# BLDC_DRV_F1.net
KiCad netlist of a schematic drawn in Altium Designer
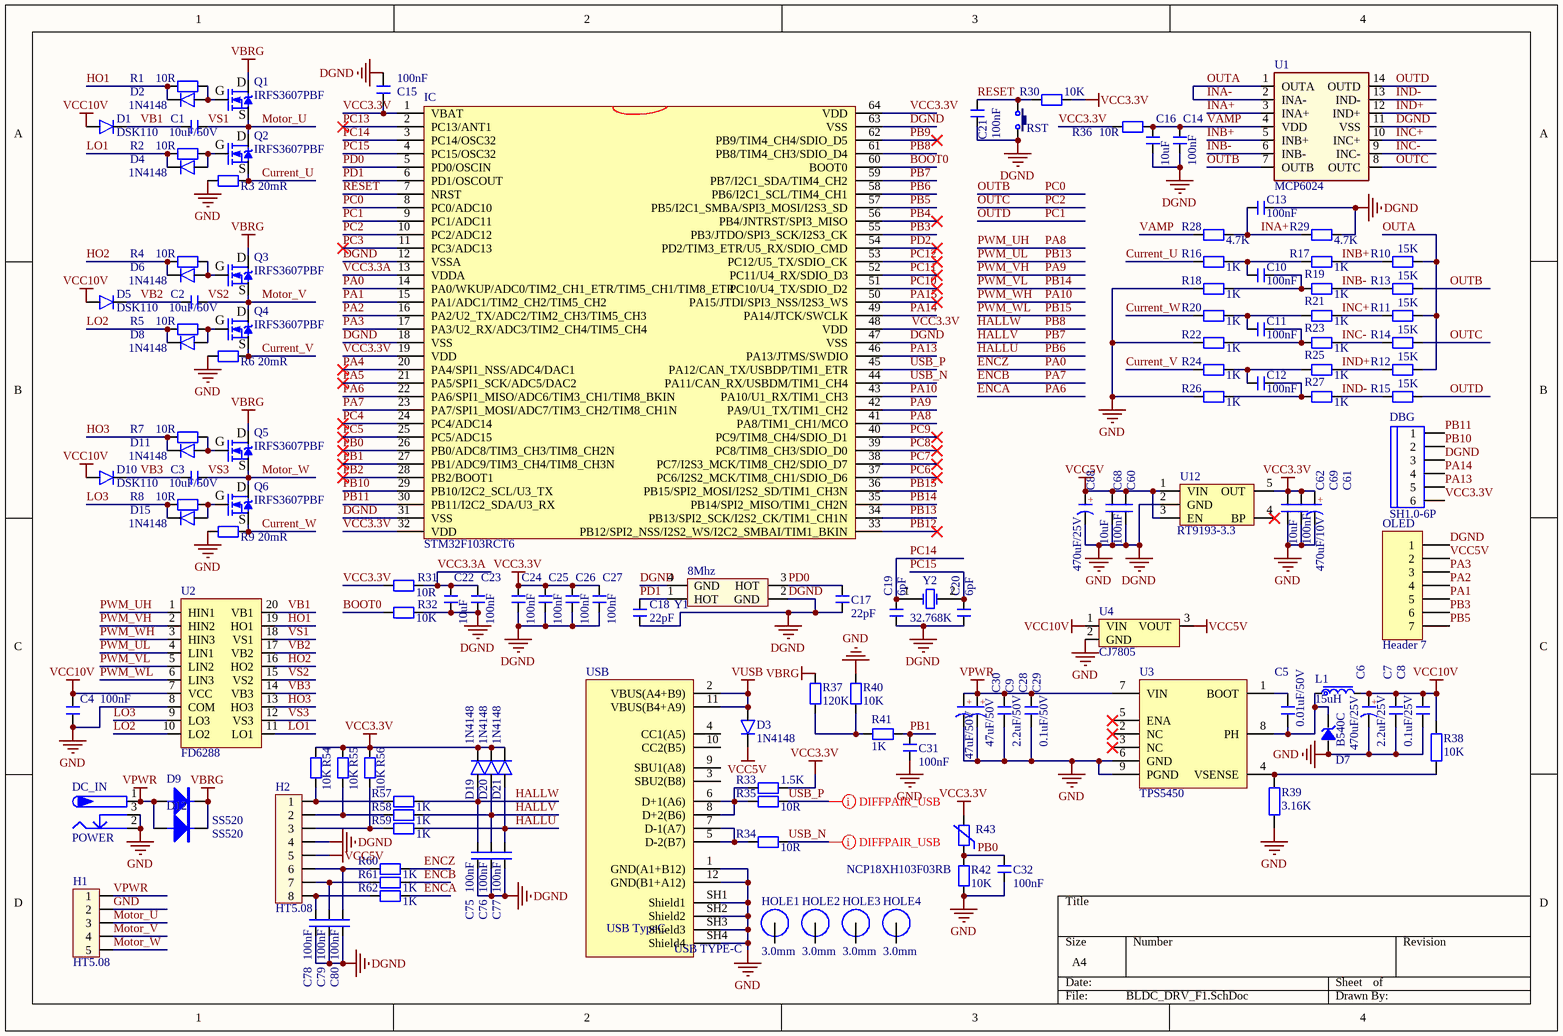
[diagram p0: BLDC_DRV_F1.SchDoc]

(export (version "E")
  (design (tool "Eeschema 10.0.6"))
  (components
    (comp (ref "C1")
      (value "10uF/50V")
      (footprint "C 0603_L")
      (description "无极性贴片电容")
      (libsource (lib "LovelessingSch") (part "C"))
    )
    (comp (ref "C2")
      (value "10uF/50V")
      (footprint "C 0603_L")
      (description "无极性贴片电容")
      (libsource (lib "LovelessingSch") (part "C"))
    )
    (comp (ref "C3")
      (value "10uF/50V")
      (footprint "C 0603_L")
      (description "无极性贴片电容")
      (libsource (lib "LovelessingSch") (part "C"))
    )
    (comp (ref "C4")
      (value "100nF")
      (footprint "C 0603_L")
      (description "无极性贴片电容")
      (fields (field (name "版权归属") "源创客"))
      (libsource (lib "电阻-电容-电感") (part "C"))
    )
    (comp (ref "C5")
      (value "0.01uF/50V")
      (footprint "C 0805_L")
      (description "无极性贴片电容")
      (libsource (lib "") (part "C_1"))
    )
    (comp (ref "C6")
      (value "470uF/25V")
      (footprint "CM D(6.3*7.7)")
      (description "贴片电解电容")
      (libsource (lib "LovelessingSch") (part "C-CM"))
    )
    (comp (ref "C7")
      (value "2.2uF/25V")
      (footprint "C 0603_L")
      (description "无极性贴片电容")
      (libsource (lib "") (part "C_1"))
    )
    (comp (ref "C8")
      (value "0.1uF/25V")
      (footprint "C 0603_L")
      (description "无极性贴片电容")
      (libsource (lib "") (part "C_1"))
    )
    (comp (ref "C9")
      (value "47uF/50V")
      (footprint "CM D(6.3*7.7)")
      (description "贴片电解电容")
      (libsource (lib "LovelessingSch") (part "C-CM"))
    )
    (comp (ref "C10")
      (value "100nF")
      (footprint "C 0603_L")
      (description "无极性贴片电容")
      (libsource (lib "LovelessingSch") (part "C"))
    )
    (comp (ref "C11")
      (value "100nF")
      (footprint "C 0603_L")
      (description "无极性贴片电容")
      (libsource (lib "LovelessingSch") (part "C"))
    )
    (comp (ref "C12")
      (value "100nF")
      (footprint "C 0603_L")
      (description "无极性贴片电容")
      (libsource (lib "LovelessingSch") (part "C"))
    )
    (comp (ref "C13")
      (value "100nF")
      (footprint "C 0603_L")
      (description "无极性贴片电容")
      (libsource (lib "LovelessingSch") (part "C"))
    )
    (comp (ref "C14")
      (value "100nF")
      (footprint "C 0603_L")
      (description "无极性贴片电容")
      (libsource (lib "LovelessingSch") (part "C"))
    )
    (comp (ref "C15")
      (value "100nF")
      (footprint "C 0603_L")
      (description "无极性贴片电容")
      (fields (field (name "版权归属") "源创客"))
      (libsource (lib "电阻-电容-电感") (part "C"))
    )
    (comp (ref "C16")
      (value "10uF")
      (footprint "C 0603_L")
      (description "无极性贴片电容")
      (libsource (lib "LovelessingSch") (part "C"))
    )
    (comp (ref "C17")
      (value "22pF")
      (footprint "C 0603_L")
      (description "无极性贴片电容")
      (libsource (lib "LovelessingSch") (part "C"))
    )
    (comp (ref "C18")
      (value "22pF")
      (footprint "C 0603_L")
      (description "无极性贴片电容")
      (libsource (lib "LovelessingSch") (part "C"))
    )
    (comp (ref "C19")
      (value "6pF")
      (footprint "C 0603_L")
      (description "无极性贴片电容")
      (libsource (lib "LovelessingSch") (part "C"))
    )
    (comp (ref "C20")
      (value "6pF")
      (footprint "C 0603_L")
      (description "无极性贴片电容")
      (libsource (lib "LovelessingSch") (part "C"))
    )
    (comp (ref "C21")
      (value "100nF")
      (footprint "C 0603_L")
      (description "无极性贴片电容")
      (libsource (lib "LovelessingSch") (part "C"))
    )
    (comp (ref "C22")
      (value "10uF")
      (footprint "C 0603_L")
      (description "无极性贴片电容")
      (libsource (lib "LovelessingSch") (part "C"))
    )
    (comp (ref "C23")
      (value "100nF")
      (footprint "C 0603_L")
      (description "无极性贴片电容")
      (libsource (lib "LovelessingSch") (part "C"))
    )
    (comp (ref "C24")
      (value "100nF")
      (footprint "C 0603_L")
      (description "无极性贴片电容")
      (libsource (lib "LovelessingSch") (part "C"))
    )
    (comp (ref "C25")
      (value "100nF")
      (footprint "C 0603_L")
      (description "无极性贴片电容")
      (libsource (lib "LovelessingSch") (part "C"))
    )
    (comp (ref "C26")
      (value "100nF")
      (footprint "C 0603_L")
      (description "无极性贴片电容")
      (libsource (lib "LovelessingSch") (part "C"))
    )
    (comp (ref "C27")
      (value "100nF")
      (footprint "C 0603_L")
      (description "无极性贴片电容")
      (libsource (lib "LovelessingSch") (part "C"))
    )
    (comp (ref "C28")
      (value "2.2uF/50V")
      (footprint "C 0805_L")
      (description "无极性贴片电容")
      (libsource (lib "") (part "C_1"))
    )
    (comp (ref "C29")
      (value "0.1uF/50V")
      (footprint "C 0805_L")
      (description "无极性贴片电容")
      (libsource (lib "") (part "C_1"))
    )
    (comp (ref "C30")
      (value "47uF/50V")
      (footprint "CM D(6.3*7.7)")
      (description "贴片电解电容")
      (libsource (lib "LovelessingSch") (part "C-CM"))
    )
    (comp (ref "C31")
      (value "100nF")
      (footprint "C 0603_L")
      (description "无极性贴片电容")
      (libsource (lib "LovelessingSch") (part "C"))
    )
    (comp (ref "C32")
      (value "100nF")
      (footprint "C 0603_L")
      (description "无极性贴片电容")
      (libsource (lib "LovelessingSch") (part "C"))
    )
    (comp (ref "C60")
      (value "100nF")
      (footprint "C 0603_L")
      (description "无极性贴片电容")
      (libsource (lib "电阻-电容-电感") (part "C"))
    )
    (comp (ref "C61")
      (value "470uF/10V")
      (footprint "CM D(6.3*7.7)")
      (description "贴片电解电容")
      (libsource (lib "LovelessingSch") (part "C-CM"))
    )
    (comp (ref "C62")
      (value "10uF")
      (footprint "C 0603_L")
      (description "无极性贴片电容")
      (libsource (lib "电阻-电容-电感") (part "C"))
    )
    (comp (ref "C68")
      (value "10uF")
      (footprint "C 0603_L")
      (description "无极性贴片电容")
      (libsource (lib "电阻-电容-电感") (part "C"))
    )
    (comp (ref "C69")
      (value "100nF")
      (footprint "C 0603_L")
      (description "无极性贴片电容")
      (libsource (lib "电阻-电容-电感") (part "C"))
    )
    (comp (ref "C75")
      (value "100nF")
      (footprint "C 0603_L")
      (description "无极性贴片电容")
      (libsource (lib "LovelessingSch") (part "C"))
    )
    (comp (ref "C76")
      (value "100nF")
      (footprint "C 0603_L")
      (description "无极性贴片电容")
      (libsource (lib "LovelessingSch") (part "C"))
    )
    (comp (ref "C77")
      (value "100nF")
      (footprint "C 0603_L")
      (description "无极性贴片电容")
      (libsource (lib "LovelessingSch") (part "C"))
    )
    (comp (ref "C78")
      (value "100nF")
      (footprint "C 0603_L")
      (description "无极性贴片电容")
      (libsource (lib "LovelessingSch") (part "C"))
    )
    (comp (ref "C79")
      (value "100nF")
      (footprint "C 0603_L")
      (description "无极性贴片电容")
      (libsource (lib "LovelessingSch") (part "C"))
    )
    (comp (ref "C80")
      (value "100nF")
      (footprint "C 0603_L")
      (description "无极性贴片电容")
      (libsource (lib "LovelessingSch") (part "C"))
    )
    (comp (ref "C88")
      (value "470uF/25V")
      (footprint "CM D(6.3*7.7)")
      (description "贴片电解电容")
      (libsource (lib "LovelessingSch") (part "C-CM"))
    )
    (comp (ref "D1")
      (value "DSK110")
      (footprint "SOD-323")
      (description "二极管")
      (libsource (lib "LovelessingSch") (part "D"))
    )
    (comp (ref "D2")
      (value "1N4148")
      (footprint "SOD-323")
      (description "二极管")
      (libsource (lib "LovelessingSch") (part "D"))
    )
    (comp (ref "D3")
      (value "1N4148")
      (footprint "SOD-323")
      (description "二极管")
      (libsource (lib "LovelessingSch") (part "D"))
    )
    (comp (ref "D4")
      (value "1N4148")
      (footprint "SOD-323")
      (description "二极管")
      (libsource (lib "LovelessingSch") (part "D"))
    )
    (comp (ref "D5")
      (value "DSK110")
      (footprint "SOD-323")
      (description "二极管")
      (libsource (lib "LovelessingSch") (part "D"))
    )
    (comp (ref "D6")
      (value "1N4148")
      (footprint "SOD-323")
      (description "二极管")
      (libsource (lib "LovelessingSch") (part "D"))
    )
    (comp (ref "D7")
      (value "B540C")
      (footprint "LovelessingPcb:SMB")
      (description "TVS二极管")
      (libsource (lib "LovelessingSch") (part "D-ZMM3V6"))
    )
    (comp (ref "D8")
      (value "1N4148")
      (footprint "SOD-323")
      (description "二极管")
      (libsource (lib "LovelessingSch") (part "D"))
    )
    (comp (ref "D9")
      (value "SS520")
      (footprint "LovelessingPcb:SMC")
      (description "整流二极管")
      (libsource (lib "LovelessingSch") (part "DIODE"))
    )
    (comp (ref "D10")
      (value "DSK110")
      (footprint "SOD-323")
      (description "二极管")
      (libsource (lib "LovelessingSch") (part "D"))
    )
    (comp (ref "D11")
      (value "1N4148")
      (footprint "SOD-323")
      (description "二极管")
      (libsource (lib "LovelessingSch") (part "D"))
    )
    (comp (ref "D12")
      (value "SS520")
      (footprint "LovelessingPcb:SMC")
      (description "整流二极管")
      (libsource (lib "LovelessingSch") (part "DIODE"))
    )
    (comp (ref "D15")
      (value "1N4148")
      (footprint "SOD-323")
      (description "二极管")
      (libsource (lib "LovelessingSch") (part "D"))
    )
    (comp (ref "D19")
      (value "1N4148")
      (footprint "SOD-323")
      (description "二极管")
      (libsource (lib "LovelessingSch") (part "D"))
    )
    (comp (ref "D20")
      (value "1N4148")
      (footprint "SOD-323")
      (description "二极管")
      (libsource (lib "LovelessingSch") (part "D"))
    )
    (comp (ref "D21")
      (value "1N4148")
      (footprint "SOD-323")
      (description "二极管")
      (libsource (lib "LovelessingSch") (part "D"))
    )
    (comp (ref "DBG") (value "SH1.0-6P") (footprint "SH1.0_6P") (libsource (lib "MiniFly ") (part "HEAD6")))
    (comp (ref "DC_IN")
      (value "POWER")
      (footprint "DC10B")
      (description "低压电源接口")
      (libsource (lib "IMX6UL_ALPHA(底板)_V2.0") (part "P-DC"))
    )
    (comp (ref "H1")
      (value "HT5.08")
      (footprint "KF7620-5P")
      (description "端子")
      (libsource (lib "LovelessingSch") (part "Header_5P"))
    )
    (comp (ref "H2")
      (value "HT5.08")
      (footprint "SH1.0 S-W-8P")
      (description "端子")
      (libsource (lib "LovelessingSch") (part "Header_8P"))
    )
    (comp (ref "HOLE1")
      (value "3.0mm")
      (footprint "M3")
      (description "螺丝焊盘")
      (fields (field (name "Comment") "HOLE"))
      (libsource (lib "LovelessingSch") (part "HOLE"))
    )
    (comp (ref "HOLE2")
      (value "3.0mm")
      (footprint "M3")
      (description "螺丝焊盘")
      (fields (field (name "Comment") "HOLE"))
      (libsource (lib "LovelessingSch") (part "HOLE"))
    )
    (comp (ref "HOLE3")
      (value "3.0mm")
      (footprint "M3")
      (description "螺丝焊盘")
      (fields (field (name "Comment") "HOLE"))
      (libsource (lib "LovelessingSch") (part "HOLE"))
    )
    (comp (ref "HOLE4")
      (value "3.0mm")
      (footprint "M3")
      (description "螺丝焊盘")
      (fields (field (name "Comment") "HOLE"))
      (libsource (lib "LovelessingSch") (part "HOLE"))
    )
    (comp (ref "IC")
      (value "STM32F103RCT6")
      (footprint "LQFP64-10*10")
      (libsource (lib "MiniSTM32 V3.0封装库") (part "STM32F103RDT6"))
    )
    (comp (ref "L1")
      (value "15uH")
      (footprint "CDRH73")
      (description "功率屏蔽电感")
      (libsource (lib "LovelessingSch") (part "L-CDRH"))
    )
    (comp (ref "OLED")
      (value "Header 7")
      (footprint "HDR2.54-M-LI-7P")
      (description "Header, 7-Pin")
      (fields (field (name "PUBLISHER") "Altium Limited"))
      (libsource (lib "Miscellaneous Connectors") (part "Header 7"))
    )
    (comp (ref "Q1")
      (value "IRFS3607PBF")
      (footprint "TO263-3B")
      (description "NMOS 75V+80A 7.4mΩ")
      (libsource (lib "LovelessingSch") (part "IRFS3607PBF"))
    )
    (comp (ref "Q2")
      (value "IRFS3607PBF")
      (footprint "TO263-3B")
      (description "NMOS 75V+80A 7.4mΩ")
      (libsource (lib "LovelessingSch") (part "IRFS3607PBF"))
    )
    (comp (ref "Q3")
      (value "IRFS3607PBF")
      (footprint "TO263-3B")
      (description "NMOS 75V+80A 7.4mΩ")
      (libsource (lib "LovelessingSch") (part "IRFS3607PBF"))
    )
    (comp (ref "Q4")
      (value "IRFS3607PBF")
      (footprint "TO263-3B")
      (description "NMOS 75V+80A 7.4mΩ")
      (libsource (lib "LovelessingSch") (part "IRFS3607PBF"))
    )
    (comp (ref "Q5")
      (value "IRFS3607PBF")
      (footprint "TO263-3B")
      (description "NMOS 75V+80A 7.4mΩ")
      (libsource (lib "LovelessingSch") (part "IRFS3607PBF"))
    )
    (comp (ref "Q6")
      (value "IRFS3607PBF")
      (footprint "TO263-3B")
      (description "NMOS 75V+80A 7.4mΩ")
      (libsource (lib "LovelessingSch") (part "IRFS3607PBF"))
    )
    (comp (ref "R1")
      (value "10R")
      (footprint "R 0603_L")
      (description "贴片电阻")
      (libsource (lib "LovelessingSch") (part "R"))
    )
    (comp (ref "R2")
      (value "10R")
      (footprint "R 0603_L")
      (description "贴片电阻")
      (libsource (lib "LovelessingSch") (part "R"))
    )
    (comp (ref "R3")
      (value "20mR")
      (footprint "R 2512_L")
      (description "贴片电阻")
      (libsource (lib "LovelessingSch") (part "R"))
    )
    (comp (ref "R4")
      (value "10R")
      (footprint "R 0603_L")
      (description "贴片电阻")
      (libsource (lib "LovelessingSch") (part "R"))
    )
    (comp (ref "R5")
      (value "10R")
      (footprint "R 0603_L")
      (description "贴片电阻")
      (libsource (lib "LovelessingSch") (part "R"))
    )
    (comp (ref "R6")
      (value "20mR")
      (footprint "R 2512_L")
      (description "贴片电阻")
      (libsource (lib "LovelessingSch") (part "R"))
    )
    (comp (ref "R7")
      (value "10R")
      (footprint "R 0603_L")
      (description "贴片电阻")
      (libsource (lib "LovelessingSch") (part "R"))
    )
    (comp (ref "R8")
      (value "10R")
      (footprint "R 0603_L")
      (description "贴片电阻")
      (libsource (lib "LovelessingSch") (part "R"))
    )
    (comp (ref "R9")
      (value "20mR")
      (footprint "R 2512_L")
      (description "贴片电阻")
      (libsource (lib "LovelessingSch") (part "R"))
    )
    (comp (ref "R10")
      (value "15K")
      (footprint "R 0603_L")
      (description "贴片电阻")
      (libsource (lib "LovelessingSch") (part "R"))
    )
    (comp (ref "R11")
      (value "15K")
      (footprint "R 0603_L")
      (description "贴片电阻")
      (libsource (lib "LovelessingSch") (part "R"))
    )
    (comp (ref "R12")
      (value "15K")
      (footprint "R 0603_L")
      (description "贴片电阻")
      (libsource (lib "LovelessingSch") (part "R"))
    )
    (comp (ref "R13")
      (value "15K")
      (footprint "R 0603_L")
      (description "贴片电阻")
      (libsource (lib "LovelessingSch") (part "R"))
    )
    (comp (ref "R14")
      (value "15K")
      (footprint "R 0603_L")
      (description "贴片电阻")
      (libsource (lib "LovelessingSch") (part "R"))
    )
    (comp (ref "R15")
      (value "15K")
      (footprint "R 0603_L")
      (description "贴片电阻")
      (libsource (lib "LovelessingSch") (part "R"))
    )
    (comp (ref "R16")
      (value "1K")
      (footprint "R 0603_L")
      (description "贴片电阻")
      (libsource (lib "LovelessingSch") (part "R"))
    )
    (comp (ref "R17")
      (value "1K")
      (footprint "R 0603_L")
      (description "贴片电阻")
      (libsource (lib "LovelessingSch") (part "R"))
    )
    (comp (ref "R18")
      (value "1K")
      (footprint "R 0603_L")
      (description "贴片电阻")
      (libsource (lib "LovelessingSch") (part "R"))
    )
    (comp (ref "R19")
      (value "1K")
      (footprint "R 0603_L")
      (description "贴片电阻")
      (libsource (lib "LovelessingSch") (part "R"))
    )
    (comp (ref "R20")
      (value "1K")
      (footprint "R 0603_L")
      (description "贴片电阻")
      (libsource (lib "LovelessingSch") (part "R"))
    )
    (comp (ref "R21")
      (value "1K")
      (footprint "R 0603_L")
      (description "贴片电阻")
      (libsource (lib "LovelessingSch") (part "R"))
    )
    (comp (ref "R22")
      (value "1K")
      (footprint "R 0603_L")
      (description "贴片电阻")
      (libsource (lib "LovelessingSch") (part "R"))
    )
    (comp (ref "R23")
      (value "1K")
      (footprint "R 0603_L")
      (description "贴片电阻")
      (libsource (lib "LovelessingSch") (part "R"))
    )
    (comp (ref "R24")
      (value "1K")
      (footprint "R 0603_L")
      (description "贴片电阻")
      (libsource (lib "LovelessingSch") (part "R"))
    )
    (comp (ref "R25")
      (value "1K")
      (footprint "R 0603_L")
      (description "贴片电阻")
      (libsource (lib "LovelessingSch") (part "R"))
    )
    (comp (ref "R26")
      (value "1K")
      (footprint "R 0603_L")
      (description "贴片电阻")
      (libsource (lib "LovelessingSch") (part "R"))
    )
    (comp (ref "R27")
      (value "1K")
      (footprint "R 0603_L")
      (description "贴片电阻")
      (libsource (lib "LovelessingSch") (part "R"))
    )
    (comp (ref "R28")
      (value "4.7K")
      (footprint "R 0603_L")
      (description "贴片电阻")
      (libsource (lib "LovelessingSch") (part "R"))
    )
    (comp (ref "R29")
      (value "4.7K")
      (footprint "R 0603_L")
      (description "贴片电阻")
      (libsource (lib "LovelessingSch") (part "R"))
    )
    (comp (ref "R30")
      (value "10K")
      (footprint "R 0603_L")
      (description "贴片电阻")
      (libsource (lib "LovelessingSch") (part "R"))
    )
    (comp (ref "R31")
      (value "10R")
      (footprint "R 0603_L")
      (description "贴片电阻")
      (libsource (lib "LovelessingSch") (part "R"))
    )
    (comp (ref "R32")
      (value "10K")
      (footprint "R 0603_L")
      (description "贴片电阻")
      (libsource (lib "LovelessingSch") (part "R"))
    )
    (comp (ref "R33")
      (value "1.5K")
      (footprint "R 0603_L")
      (description "贴片电阻")
      (libsource (lib "LovelessingSch") (part "R"))
    )
    (comp (ref "R34")
      (value "10R")
      (footprint "R 0603_L")
      (description "贴片电阻")
      (libsource (lib "LovelessingSch") (part "R"))
    )
    (comp (ref "R35")
      (value "10R")
      (footprint "R 0603_L")
      (description "贴片电阻")
      (libsource (lib "LovelessingSch") (part "R"))
    )
    (comp (ref "R36")
      (value "10R")
      (footprint "R 0603_L")
      (description "贴片电阻")
      (libsource (lib "LovelessingSch") (part "R"))
    )
    (comp (ref "R37")
      (value "120K")
      (footprint "R 0603_L")
      (description "贴片电阻")
      (libsource (lib "LovelessingSch") (part "R"))
    )
    (comp (ref "R38")
      (value "10K")
      (footprint "R 0603_L")
      (description "贴片电阻")
      (libsource (lib "") (part "R_1"))
    )
    (comp (ref "R39")
      (value "3.16K")
      (footprint "R 0603_L")
      (description "贴片电阻")
      (libsource (lib "") (part "R_1"))
    )
    (comp (ref "R40")
      (value "10K")
      (footprint "R 0603_L")
      (description "贴片电阻")
      (libsource (lib "LovelessingSch") (part "R"))
    )
    (comp (ref "R41")
      (value "1K")
      (footprint "R 0603_L")
      (description "贴片电阻")
      (libsource (lib "LovelessingSch") (part "R"))
    )
    (comp (ref "R42")
      (value "10K")
      (footprint "R 0603_L")
      (description "贴片电阻")
      (libsource (lib "LovelessingSch") (part "R"))
    )
    (comp (ref "R43")
      (value "NCP18XH103F03RB")
      (footprint "R 0603_L")
      (description "热敏电阻")
      (libsource (lib "LovelessingSch") (part "R_NTC"))
    )
    (comp (ref "R54")
      (value "10K")
      (footprint "R 0603_L")
      (description "贴片电阻")
      (libsource (lib "LovelessingSch") (part "R"))
    )
    (comp (ref "R55")
      (value "10K")
      (footprint "R 0603_L")
      (description "贴片电阻")
      (libsource (lib "LovelessingSch") (part "R"))
    )
    (comp (ref "R56")
      (value "10K")
      (footprint "R 0603_L")
      (description "贴片电阻")
      (libsource (lib "LovelessingSch") (part "R"))
    )
    (comp (ref "R57")
      (value "1K")
      (footprint "R 0603_L")
      (description "贴片电阻")
      (libsource (lib "LovelessingSch") (part "R"))
    )
    (comp (ref "R58")
      (value "1K")
      (footprint "R 0603_L")
      (description "贴片电阻")
      (libsource (lib "LovelessingSch") (part "R"))
    )
    (comp (ref "R59")
      (value "1K")
      (footprint "R 0603_L")
      (description "贴片电阻")
      (libsource (lib "LovelessingSch") (part "R"))
    )
    (comp (ref "R60")
      (value "1K")
      (footprint "R 0603_L")
      (description "贴片电阻")
      (libsource (lib "LovelessingSch") (part "R"))
    )
    (comp (ref "R61")
      (value "1K")
      (footprint "R 0603_L")
      (description "贴片电阻")
      (libsource (lib "LovelessingSch") (part "R"))
    )
    (comp (ref "R62")
      (value "1K")
      (footprint "R 0603_L")
      (description "贴片电阻")
      (libsource (lib "LovelessingSch") (part "R"))
    )
    (comp (ref "RST")
      (value "KEY")
      (footprint "TSW SMD-3*6*2.5")
      (description "按键")
      (libsource (lib "LovelessingSch") (part "KEY"))
    )
    (comp (ref "U1") (value "MCP6024") (footprint "SOP14_L") (libsource (lib "MINIBLDC") (part "MCP6024")))
    (comp (ref "U2") (value "FD6288") (footprint "TSSOP20_L") (libsource (lib "MINIBLDC") (part "FD6288")))
    (comp (ref "U3")
      (value "TPS5450")
      (footprint "SOP8_G")
      (description "降压电源芯片")
      (libsource (lib "Schlib1") (part "TPS5450"))
    )
    (comp (ref "U4")
      (value "CJ7805")
      (footprint "TO263_3B")
      (description "7805 5V")
      (libsource (lib "LovelessingSch") (part "CJ7805"))
    )
    (comp (ref "U12")
      (value "RT9193-3.3")
      (footprint "SOT23-5L")
      (description "LDO")
      (libsource (lib "LDO和DCDC") (part "LDO RT9193"))
    )
    (comp (ref "USB")
      (value "USB TypeC")
      (footprint "USB Type-C")
      (description "12P TypeC 母座")
      (libsource (lib "正点原子封装库V1.0") (part "USB 2.0 Type C"))
    )
    (comp (ref "Y1")
      (value "8Mhz")
      (footprint "XTAL-3225")
      (description "3225贴片无源晶振")
      (libsource (lib "ALIENTEK_COMPONENT") (part "XTAL_3225"))
    )
    (comp (ref "Y2")
      (value "32.768K")
      (footprint "OSC 3215-2P")
      (description "Crystal Oscillator")
      (fields (field (name "PUBLISHER") "Altium Limited"))
      (libsource (lib "WarShip V3 STM32103封装库") (part "XTAL"))
    )
  )
  (nets
    (net (code "1") (name "/BOOT0") (class "Default")
      (node (ref "IC") (pin "60") (pinfunction "BOOT0_60") (pintype "passive"))
      (node (ref "R32") (pin "1") (pinfunction "1_1") (pintype "passive"))
    )
    (net (code "2") (name "/Current_U") (class "Default")
      (node (ref "Q2") (pin "3") (pinfunction "S_3") (pintype "passive"))
      (node (ref "R16") (pin "1") (pinfunction "1_1") (pintype "passive"))
      (node (ref "R3") (pin "2") (pinfunction "2_2") (pintype "passive"))
    )
    (net (code "3") (name "/Current_V") (class "Default")
      (node (ref "Q4") (pin "3") (pinfunction "S_3") (pintype "passive"))
      (node (ref "R24") (pin "1") (pinfunction "1_1") (pintype "passive"))
      (node (ref "R6") (pin "2") (pinfunction "2_2") (pintype "passive"))
    )
    (net (code "4") (name "/Current_W") (class "Default")
      (node (ref "Q6") (pin "3") (pinfunction "S_3") (pintype "passive"))
      (node (ref "R20") (pin "1") (pinfunction "1_1") (pintype "passive"))
      (node (ref "R9") (pin "2") (pinfunction "2_2") (pintype "passive"))
    )
    (net (code "5") (name "/ENCA") (class "Default")
      (node (ref "IC") (pin "22") (pinfunction "PA6/SPI1_MISO/ADC6/TIM3_CH1/TIM8_BKIN_22") (pintype "passive"))
      (node (ref "R62") (pin "2") (pinfunction "2_2") (pintype "passive"))
    )
    (net (code "6") (name "/ENCB") (class "Default")
      (node (ref "IC") (pin "23") (pinfunction "PA7/SPI1_MOSI/ADC7/TIM3_CH2/TIM8_CH1N_23") (pintype "passive"))
      (node (ref "R61") (pin "2") (pinfunction "2_2") (pintype "passive"))
    )
    (net (code "7") (name "/ENCZ") (class "Default")
      (node (ref "IC") (pin "14") (pinfunction "PA0/WKUP/ADC0/TIM2_CH1_ETR/TIM5_CH1/TIM8_ETR_14") (pintype "passive"))
      (node (ref "R60") (pin "2") (pinfunction "2_2") (pintype "passive"))
    )
    (net (code "8") (name "/HALLU") (class "Default")
      (node (ref "C77") (pin "1") (pinfunction "1_1") (pintype "passive"))
      (node (ref "D21") (pin "1") (pintype "passive"))
      (node (ref "IC") (pin "58") (pinfunction "PB6/I2C1_SCL/TIM4_CH1_58") (pintype "passive"))
      (node (ref "R59") (pin "2") (pinfunction "2_2") (pintype "passive"))
    )
    (net (code "9") (name "/HALLV") (class "Default")
      (node (ref "C76") (pin "1") (pinfunction "1_1") (pintype "passive"))
      (node (ref "D20") (pin "1") (pintype "passive"))
      (node (ref "IC") (pin "59") (pinfunction "PB7/I2C1_SDA/TIM4_CH2_59") (pintype "passive"))
      (node (ref "R58") (pin "2") (pinfunction "2_2") (pintype "passive"))
    )
    (net (code "10") (name "/HALLW") (class "Default")
      (node (ref "C75") (pin "1") (pinfunction "1_1") (pintype "passive"))
      (node (ref "D19") (pin "1") (pintype "passive"))
      (node (ref "IC") (pin "61") (pinfunction "PB8/TIM4_CH3/SDIO_D4_61") (pintype "passive"))
      (node (ref "R57") (pin "2") (pinfunction "2_2") (pintype "passive"))
    )
    (net (code "11") (name "/HO1") (class "Default")
      (node (ref "D2") (pin "2") (pintype "passive"))
      (node (ref "R1") (pin "1") (pinfunction "1_1") (pintype "passive"))
      (node (ref "U2") (pin "19") (pinfunction "HO1_19") (pintype "passive"))
    )
    (net (code "12") (name "/HO2") (class "Default")
      (node (ref "D6") (pin "2") (pintype "passive"))
      (node (ref "R4") (pin "1") (pinfunction "1_1") (pintype "passive"))
      (node (ref "U2") (pin "16") (pinfunction "HO2_16") (pintype "passive"))
    )
    (net (code "13") (name "/HO3") (class "Default")
      (node (ref "D11") (pin "2") (pintype "passive"))
      (node (ref "R7") (pin "1") (pinfunction "1_1") (pintype "passive"))
      (node (ref "U2") (pin "13") (pinfunction "HO3_13") (pintype "passive"))
    )
    (net (code "14") (name "/INA+") (class "Default")
      (node (ref "C13") (pin "1") (pinfunction "1_1") (pintype "passive"))
      (node (ref "R28") (pin "2") (pinfunction "2_2") (pintype "passive"))
      (node (ref "R29") (pin "1") (pinfunction "1_1") (pintype "passive"))
      (node (ref "U1") (pin "3") (pinfunction "INA+_3") (pintype "passive"))
    )
    (net (code "15") (name "/INA-") (class "Default")
      (node (ref "R10") (pin "2") (pinfunction "2_2") (pintype "passive"))
      (node (ref "R11") (pin "2") (pinfunction "2_2") (pintype "passive"))
      (node (ref "R12") (pin "2") (pinfunction "2_2") (pintype "passive"))
      (node (ref "U1") (pin "1") (pinfunction "OUTA_1") (pintype "passive"))
      (node (ref "U1") (pin "2") (pinfunction "INA-_2") (pintype "passive"))
    )
    (net (code "16") (name "/INB+") (class "Default")
      (node (ref "R10") (pin "1") (pinfunction "1_1") (pintype "passive"))
      (node (ref "R17") (pin "2") (pinfunction "2_2") (pintype "passive"))
      (node (ref "U1") (pin "5") (pinfunction "INB+_5") (pintype "passive"))
    )
    (net (code "17") (name "/INB-") (class "Default")
      (node (ref "R13") (pin "1") (pinfunction "1_1") (pintype "passive"))
      (node (ref "R19") (pin "2") (pinfunction "2_2") (pintype "passive"))
      (node (ref "U1") (pin "6") (pinfunction "INB-_6") (pintype "passive"))
    )
    (net (code "18") (name "/INC+") (class "Default")
      (node (ref "R11") (pin "1") (pinfunction "1_1") (pintype "passive"))
      (node (ref "R21") (pin "2") (pinfunction "2_2") (pintype "passive"))
      (node (ref "U1") (pin "10") (pinfunction "INC+_10") (pintype "passive"))
    )
    (net (code "19") (name "/INC-") (class "Default")
      (node (ref "R14") (pin "1") (pinfunction "1_1") (pintype "passive"))
      (node (ref "R23") (pin "2") (pinfunction "2_2") (pintype "passive"))
      (node (ref "U1") (pin "9") (pinfunction "INC-_9") (pintype "passive"))
    )
    (net (code "20") (name "/IND+") (class "Default")
      (node (ref "R12") (pin "1") (pinfunction "1_1") (pintype "passive"))
      (node (ref "R25") (pin "2") (pinfunction "2_2") (pintype "passive"))
      (node (ref "U1") (pin "12") (pinfunction "IND+_12") (pintype "passive"))
    )
    (net (code "21") (name "/IND-") (class "Default")
      (node (ref "R15") (pin "1") (pinfunction "1_1") (pintype "passive"))
      (node (ref "R27") (pin "2") (pinfunction "2_2") (pintype "passive"))
      (node (ref "U1") (pin "13") (pinfunction "IND-_13") (pintype "passive"))
    )
    (net (code "22") (name "/LO1") (class "Default")
      (node (ref "D4") (pin "2") (pintype "passive"))
      (node (ref "R2") (pin "1") (pinfunction "1_1") (pintype "passive"))
      (node (ref "U2") (pin "11") (pinfunction "LO1_11") (pintype "passive"))
    )
    (net (code "23") (name "/LO2") (class "Default")
      (node (ref "D8") (pin "2") (pintype "passive"))
      (node (ref "R5") (pin "1") (pinfunction "1_1") (pintype "passive"))
      (node (ref "U2") (pin "10") (pinfunction "LO2_10") (pintype "passive"))
    )
    (net (code "24") (name "/LO3") (class "Default")
      (node (ref "D15") (pin "2") (pintype "passive"))
      (node (ref "R8") (pin "1") (pinfunction "1_1") (pintype "passive"))
      (node (ref "U2") (pin "9") (pinfunction "LO3_9") (pintype "passive"))
    )
    (net (code "25") (name "/Motor_U") (class "Default")
      (node (ref "C1") (pin "1") (pinfunction "1_1") (pintype "passive"))
      (node (ref "H1") (pin "3") (pinfunction "3_3") (pintype "passive"))
      (node (ref "Q1") (pin "3") (pinfunction "S_3") (pintype "passive"))
      (node (ref "Q2") (pin "2") (pinfunction "D_2") (pintype "passive"))
      (node (ref "U2") (pin "18") (pinfunction "VS1_18") (pintype "passive"))
    )
    (net (code "26") (name "/Motor_V") (class "Default")
      (node (ref "C2") (pin "1") (pinfunction "1_1") (pintype "passive"))
      (node (ref "H1") (pin "4") (pinfunction "4_4") (pintype "passive"))
      (node (ref "Q3") (pin "3") (pinfunction "S_3") (pintype "passive"))
      (node (ref "Q4") (pin "2") (pinfunction "D_2") (pintype "passive"))
      (node (ref "U2") (pin "15") (pinfunction "VS2_15") (pintype "passive"))
    )
    (net (code "27") (name "/Motor_W") (class "Default")
      (node (ref "C3") (pin "1") (pinfunction "1_1") (pintype "passive"))
      (node (ref "H1") (pin "5") (pinfunction "5_5") (pintype "passive"))
      (node (ref "Q5") (pin "3") (pinfunction "S_3") (pintype "passive"))
      (node (ref "Q6") (pin "2") (pinfunction "D_2") (pintype "passive"))
      (node (ref "U2") (pin "12") (pinfunction "VS3_12") (pintype "passive"))
    )
    (net (code "28") (name "/OUTB") (class "Default")
      (node (ref "IC") (pin "8") (pinfunction "PC0/ADC10_8") (pintype "passive"))
      (node (ref "R13") (pin "2") (pinfunction "2_2") (pintype "passive"))
      (node (ref "U1") (pin "7") (pinfunction "OUTB_7") (pintype "passive"))
    )
    (net (code "29") (name "/OUTC") (class "Default")
      (node (ref "IC") (pin "10") (pinfunction "PC2/ADC12_10") (pintype "passive"))
      (node (ref "R14") (pin "2") (pinfunction "2_2") (pintype "passive"))
      (node (ref "U1") (pin "8") (pinfunction "OUTC_8") (pintype "passive"))
    )
    (net (code "30") (name "/OUTD") (class "Default")
      (node (ref "IC") (pin "9") (pinfunction "PC1/ADC11_9") (pintype "passive"))
      (node (ref "R15") (pin "2") (pinfunction "2_2") (pintype "passive"))
      (node (ref "U1") (pin "14") (pinfunction "OUTD_14") (pintype "passive"))
    )
    (net (code "31") (name "/PA1") (class "Default")
      (node (ref "IC") (pin "15") (pinfunction "PA1/ADC1/TIM2_CH2/TIM5_CH2_15") (pintype "passive"))
      (node (ref "OLED") (pin "5") (pinfunction "5_5") (pintype "passive"))
    )
    (net (code "32") (name "/PA2") (class "Default")
      (node (ref "IC") (pin "16") (pinfunction "PA2/U2_TX/ADC2/TIM2_CH3/TIM5_CH3_16") (pintype "passive"))
      (node (ref "OLED") (pin "4") (pinfunction "4_4") (pintype "passive"))
    )
    (net (code "33") (name "/PA3") (class "Default")
      (node (ref "IC") (pin "17") (pinfunction "PA3/U2_RX/ADC3/TIM2_CH4/TIM5_CH4_17") (pintype "passive"))
      (node (ref "OLED") (pin "3") (pinfunction "3_3") (pintype "passive"))
    )
    (net (code "34") (name "/PA4") (class "Default")
      (node (ref "IC") (pin "20") (pinfunction "PA4/SPI1_NSS/ADC4/DAC1_20") (pintype "passive+no_connect"))
    )
    (net (code "35") (name "/PA5") (class "Default")
      (node (ref "IC") (pin "21") (pinfunction "PA5/SPI1_SCK/ADC5/DAC2_21") (pintype "passive+no_connect"))
    )
    (net (code "36") (name "/PA8") (class "Default")
      (node (ref "IC") (pin "41") (pinfunction "PA8/TIM1_CH1/MCO_41") (pintype "passive"))
      (node (ref "U2") (pin "1") (pinfunction "HIN1_1") (pintype "passive"))
    )
    (net (code "37") (name "/PA9") (class "Default")
      (node (ref "IC") (pin "42") (pinfunction "PA9/U1_TX/TIM1_CH2_42") (pintype "passive"))
      (node (ref "U2") (pin "2") (pinfunction "HIN2_2") (pintype "passive"))
    )
    (net (code "38") (name "/PA10") (class "Default")
      (node (ref "IC") (pin "43") (pinfunction "PA10/U1_RX/TIM1_CH3_43") (pintype "passive"))
      (node (ref "U2") (pin "3") (pinfunction "HIN3_3") (pintype "passive"))
    )
    (net (code "39") (name "/PA13") (class "Default")
      (node (ref "DBG") (pin "5") (pinfunction "5_5") (pintype "passive"))
      (node (ref "IC") (pin "46") (pinfunction "PA13/JTMS/SWDIO_46") (pintype "passive"))
    )
    (net (code "40") (name "/PA14") (class "Default")
      (node (ref "DBG") (pin "4") (pinfunction "4_4") (pintype "passive"))
      (node (ref "IC") (pin "49") (pinfunction "PA14/JTCK/SWCLK_49") (pintype "passive"))
    )
    (net (code "41") (name "/PA15") (class "Default")
      (node (ref "IC") (pin "50") (pinfunction "PA15/JTDI/SPI3_NSS/I2S3_WS_50") (pintype "passive+no_connect"))
    )
    (net (code "42") (name "/PB0") (class "Default")
      (node (ref "C32") (pin "2") (pinfunction "2_2") (pintype "passive"))
      (node (ref "IC") (pin "26") (pinfunction "PB0/ADC8/TIM3_CH3/TIM8_CH2N_26") (pintype "passive"))
      (node (ref "R42") (pin "2") (pinfunction "2_2") (pintype "passive"))
      (node (ref "R43") (pin "1") (pinfunction "1_1") (pintype "passive"))
    )
    (net (code "43") (name "/PB1") (class "Default")
      (node (ref "C31") (pin "2") (pinfunction "2_2") (pintype "passive"))
      (node (ref "IC") (pin "27") (pinfunction "PB1/ADC9/TIM3_CH4/TIM8_CH3N_27") (pintype "passive"))
      (node (ref "R41") (pin "1") (pinfunction "1_1") (pintype "passive"))
    )
    (net (code "44") (name "/PB2") (class "Default")
      (node (ref "IC") (pin "28") (pinfunction "PB2/BOOT1_28") (pintype "passive+no_connect"))
    )
    (net (code "45") (name "/PB3") (class "Default")
      (node (ref "IC") (pin "55") (pinfunction "PB3/JTDO/SPI3_SCK/I2S3_CK_55") (pintype "passive"))
      (node (ref "OLED") (pin "6") (pinfunction "6_6") (pintype "passive"))
    )
    (net (code "46") (name "/PB4") (class "Default")
      (node (ref "IC") (pin "56") (pinfunction "PB4/JNTRST/SPI3_MISO_56") (pintype "passive+no_connect"))
    )
    (net (code "47") (name "/PB5") (class "Default")
      (node (ref "IC") (pin "57") (pinfunction "PB5/I2C1_SMBA/SPI3_MOSI/I2S3_SD_57") (pintype "passive"))
      (node (ref "OLED") (pin "7") (pinfunction "7_7") (pintype "passive"))
    )
    (net (code "48") (name "/PB9") (class "Default")
      (node (ref "IC") (pin "62") (pinfunction "PB9/TIM4_CH4/SDIO_D5_62") (pintype "passive+no_connect"))
    )
    (net (code "49") (name "/PB10") (class "Default")
      (node (ref "DBG") (pin "2") (pinfunction "2_2") (pintype "passive"))
      (node (ref "IC") (pin "29") (pinfunction "PB10/I2C2_SCL/U3_TX_29") (pintype "passive"))
    )
    (net (code "50") (name "/PB11") (class "Default")
      (node (ref "DBG") (pin "1") (pinfunction "1_1") (pintype "passive"))
      (node (ref "IC") (pin "30") (pinfunction "PB11/I2C2_SDA/U3_RX_30") (pintype "passive"))
    )
    (net (code "51") (name "/PB12") (class "Default")
      (node (ref "IC") (pin "33") (pinfunction "PB12/SPI2_NSS/I2S2_WS/I2C2_SMBAI/TIM1_BKIN_33") (pintype "passive+no_connect"))
    )
    (net (code "52") (name "/PB13") (class "Default")
      (node (ref "IC") (pin "34") (pinfunction "PB13/SPI2_SCK/I2S2_CK/TIM1_CH1N_34") (pintype "passive"))
      (node (ref "U2") (pin "4") (pinfunction "LIN1_4") (pintype "passive"))
    )
    (net (code "53") (name "/PB14") (class "Default")
      (node (ref "IC") (pin "35") (pinfunction "PB14/SPI2_MISO/TIM1_CH2N_35") (pintype "passive"))
      (node (ref "U2") (pin "5") (pinfunction "LIN2_5") (pintype "passive"))
    )
    (net (code "54") (name "/PB15") (class "Default")
      (node (ref "IC") (pin "36") (pinfunction "PB15/SPI2_MOSI/I2S2_SD/TIM1_CH3N_36") (pintype "passive"))
      (node (ref "U2") (pin "6") (pinfunction "LIN3_6") (pintype "passive"))
    )
    (net (code "55") (name "/PC3") (class "Default")
      (node (ref "IC") (pin "11") (pinfunction "PC3/ADC13_11") (pintype "passive+no_connect"))
    )
    (net (code "56") (name "/PC4") (class "Default")
      (node (ref "IC") (pin "24") (pinfunction "PC4/ADC14_24") (pintype "passive+no_connect"))
    )
    (net (code "57") (name "/PC5") (class "Default")
      (node (ref "IC") (pin "25") (pinfunction "PC5/ADC15_25") (pintype "passive+no_connect"))
    )
    (net (code "58") (name "/PC6") (class "Default")
      (node (ref "IC") (pin "37") (pinfunction "PC6/I2S2_MCK/TIM8_CH1/SDIO_D6_37") (pintype "passive+no_connect"))
    )
    (net (code "59") (name "/PC7") (class "Default")
      (node (ref "IC") (pin "38") (pinfunction "PC7/I2S3_MCK/TIM8_CH2/SDIO_D7_38") (pintype "passive+no_connect"))
    )
    (net (code "60") (name "/PC8") (class "Default")
      (node (ref "IC") (pin "39") (pinfunction "PC8/TIM8_CH3/SDIO_D0_39") (pintype "passive+no_connect"))
    )
    (net (code "61") (name "/PC9") (class "Default")
      (node (ref "IC") (pin "40") (pinfunction "PC9/TIM8_CH4/SDIO_D1_40") (pintype "passive+no_connect"))
    )
    (net (code "62") (name "/PC10") (class "Default")
      (node (ref "IC") (pin "51") (pinfunction "PC10/U4_TX/SDIO_D2_51") (pintype "passive+no_connect"))
    )
    (net (code "63") (name "/PC11") (class "Default")
      (node (ref "IC") (pin "52") (pinfunction "PC11/U4_RX/SDIO_D3_52") (pintype "passive+no_connect"))
    )
    (net (code "64") (name "/PC12") (class "Default")
      (node (ref "IC") (pin "53") (pinfunction "PC12/U5_TX/SDIO_CK_53") (pintype "passive+no_connect"))
    )
    (net (code "65") (name "/PC13") (class "Default")
      (node (ref "IC") (pin "2") (pinfunction "PC13/ANT1_2") (pintype "passive+no_connect"))
    )
    (net (code "66") (name "/PC14") (class "Default")
      (node (ref "C19") (pin "2") (pinfunction "2_2") (pintype "passive"))
      (node (ref "IC") (pin "3") (pinfunction "PC14/OSC32_3") (pintype "passive"))
      (node (ref "Y2") (pin "1") (pinfunction "OSC1_1") (pintype "passive"))
    )
    (net (code "67") (name "/PC15") (class "Default")
      (node (ref "C20") (pin "2") (pinfunction "2_2") (pintype "passive"))
      (node (ref "IC") (pin "4") (pinfunction "PC15/OSC32_4") (pintype "passive"))
      (node (ref "Y2") (pin "2") (pinfunction "OSC2_2") (pintype "passive"))
    )
    (net (code "68") (name "/PD0") (class "Default")
      (node (ref "C17") (pin "2") (pinfunction "2_2") (pintype "passive"))
      (node (ref "IC") (pin "5") (pinfunction "PD0/OSCIN_5") (pintype "passive"))
      (node (ref "Y1") (pin "3") (pinfunction "HOT_3") (pintype "passive"))
    )
    (net (code "69") (name "/PD1") (class "Default")
      (node (ref "C18") (pin "2") (pinfunction "2_2") (pintype "passive"))
      (node (ref "IC") (pin "6") (pinfunction "PD1/OSCOUT_6") (pintype "passive"))
      (node (ref "Y1") (pin "1") (pinfunction "HOT_1") (pintype "passive"))
    )
    (net (code "70") (name "/PD2") (class "Default")
      (node (ref "IC") (pin "54") (pinfunction "PD2/TIM3_ETR/U5_RX/SDIO_CMD_54") (pintype "passive+no_connect"))
    )
    (net (code "71") (name "/RESET") (class "Default")
      (node (ref "C21") (pin "1") (pinfunction "1_1") (pintype "passive"))
      (node (ref "IC") (pin "7") (pinfunction "NRST_7") (pintype "passive"))
      (node (ref "R30") (pin "1") (pinfunction "1_1") (pintype "passive"))
      (node (ref "RST") (pin "1") (pinfunction "1_1") (pintype "passive"))
    )
    (net (code "72") (name "/USB_N") (class "Default")
      (node (ref "IC") (pin "44") (pinfunction "PA11/CAN_RX/USBDM/TIM1_CH4_44") (pintype "passive"))
      (node (ref "R34") (pin "2") (pinfunction "2_2") (pintype "passive"))
    )
    (net (code "73") (name "/USB_P") (class "Default")
      (node (ref "IC") (pin "45") (pinfunction "PA12/CAN_TX/USBDP/TIM1_ETR_45") (pintype "passive"))
      (node (ref "R35") (pin "2") (pinfunction "2_2") (pintype "passive"))
    )
    (net (code "74") (name "/VAMP") (class "Default")
      (node (ref "C14") (pin "1") (pinfunction "1_1") (pintype "passive"))
      (node (ref "C16") (pin "1") (pinfunction "1_1") (pintype "passive"))
      (node (ref "R28") (pin "1") (pinfunction "1_1") (pintype "passive"))
      (node (ref "R36") (pin "2") (pinfunction "2_2") (pintype "passive"))
      (node (ref "U1") (pin "4") (pinfunction "VDD_4") (pintype "passive"))
    )
    (net (code "75") (name "/VB1") (class "Default")
      (node (ref "C1") (pin "2") (pinfunction "2_2") (pintype "passive"))
      (node (ref "D1") (pin "2") (pintype "passive"))
      (node (ref "U2") (pin "20") (pinfunction "VB1_20") (pintype "passive"))
    )
    (net (code "76") (name "/VB2") (class "Default")
      (node (ref "C2") (pin "2") (pinfunction "2_2") (pintype "passive"))
      (node (ref "D5") (pin "2") (pintype "passive"))
      (node (ref "U2") (pin "17") (pinfunction "VB2_17") (pintype "passive"))
    )
    (net (code "77") (name "/VB3") (class "Default")
      (node (ref "C3") (pin "2") (pinfunction "2_2") (pintype "passive"))
      (node (ref "D10") (pin "2") (pintype "passive"))
      (node (ref "U2") (pin "14") (pinfunction "VB3_14") (pintype "passive"))
    )
    (net (code "78") (name "/VCC3.3A") (class "Default")
      (node (ref "C22") (pin "1") (pinfunction "1_1") (pintype "passive"))
      (node (ref "C23") (pin "1") (pinfunction "1_1") (pintype "passive"))
      (node (ref "IC") (pin "13") (pinfunction "VDDA_13") (pintype "passive"))
      (node (ref "R31") (pin "2") (pinfunction "2_2") (pintype "passive"))
    )
    (net (code "79") (name "DGND") (class "Default")
      (node (ref "C13") (pin "2") (pinfunction "2_2") (pintype "passive"))
      (node (ref "C14") (pin "2") (pinfunction "2_2") (pintype "passive"))
      (node (ref "C15") (pin "2") (pinfunction "2_2") (pintype "passive"))
      (node (ref "C16") (pin "2") (pinfunction "2_2") (pintype "passive"))
      (node (ref "C17") (pin "1") (pinfunction "1_1") (pintype "passive"))
      (node (ref "C18") (pin "1") (pinfunction "1_1") (pintype "passive"))
      (node (ref "C19") (pin "1") (pinfunction "1_1") (pintype "passive"))
      (node (ref "C20") (pin "1") (pinfunction "1_1") (pintype "passive"))
      (node (ref "C21") (pin "2") (pinfunction "2_2") (pintype "passive"))
      (node (ref "C22") (pin "2") (pinfunction "2_2") (pintype "passive"))
      (node (ref "C23") (pin "2") (pinfunction "2_2") (pintype "passive"))
      (node (ref "C24") (pin "2") (pinfunction "2_2") (pintype "passive"))
      (node (ref "C25") (pin "2") (pinfunction "2_2") (pintype "passive"))
      (node (ref "C26") (pin "2") (pinfunction "2_2") (pintype "passive"))
      (node (ref "C27") (pin "2") (pinfunction "2_2") (pintype "passive"))
      (node (ref "C28") (pin "1") (pinfunction "1_1") (pintype "passive"))
      (node (ref "C29") (pin "1") (pinfunction "1_1") (pintype "passive"))
      (node (ref "C30") (pin "2") (pinfunction "K_2") (pintype "passive"))
      (node (ref "C31") (pin "1") (pinfunction "1_1") (pintype "passive"))
      (node (ref "C32") (pin "1") (pinfunction "1_1") (pintype "passive"))
      (node (ref "C4") (pin "1") (pinfunction "1_1") (pintype "passive"))
      (node (ref "C6") (pin "2") (pinfunction "K_2") (pintype "passive"))
      (node (ref "C60") (pin "2") (pinfunction "2_2") (pintype "passive"))
      (node (ref "C61") (pin "2") (pinfunction "K_2") (pintype "passive"))
      (node (ref "C62") (pin "2") (pinfunction "2_2") (pintype "passive"))
      (node (ref "C68") (pin "2") (pinfunction "2_2") (pintype "passive"))
      (node (ref "C69") (pin "2") (pinfunction "2_2") (pintype "passive"))
      (node (ref "C7") (pin "1") (pinfunction "1_1") (pintype "passive"))
      (node (ref "C75") (pin "2") (pinfunction "2_2") (pintype "passive"))
      (node (ref "C76") (pin "2") (pinfunction "2_2") (pintype "passive"))
      (node (ref "C77") (pin "2") (pinfunction "2_2") (pintype "passive"))
      (node (ref "C78") (pin "2") (pinfunction "2_2") (pintype "passive"))
      (node (ref "C79") (pin "2") (pinfunction "2_2") (pintype "passive"))
      (node (ref "C8") (pin "1") (pinfunction "1_1") (pintype "passive"))
      (node (ref "C80") (pin "2") (pinfunction "2_2") (pintype "passive"))
      (node (ref "C88") (pin "2") (pinfunction "K_2") (pintype "passive"))
      (node (ref "C9") (pin "2") (pinfunction "K_2") (pintype "passive"))
      (node (ref "D7") (pin "1") (pintype "passive"))
      (node (ref "DBG") (pin "3") (pinfunction "3_3") (pintype "passive"))
      (node (ref "DC_IN") (pin "2") (pintype "power_in"))
      (node (ref "DC_IN") (pin "3") (pintype "power_in"))
      (node (ref "H1") (pin "2") (pinfunction "2_2") (pintype "passive"))
      (node (ref "H2") (pin "4") (pinfunction "4_4") (pintype "passive"))
      (node (ref "IC") (pin "12") (pinfunction "VSSA_12") (pintype "passive"))
      (node (ref "IC") (pin "18") (pinfunction "VSS_18") (pintype "passive"))
      (node (ref "IC") (pin "31") (pinfunction "VSS_31") (pintype "passive"))
      (node (ref "IC") (pin "47") (pinfunction "VSS_47") (pintype "passive"))
      (node (ref "IC") (pin "63") (pinfunction "VSS_63") (pintype "passive"))
      (node (ref "OLED") (pin "1") (pinfunction "1_1") (pintype "passive"))
      (node (ref "R18") (pin "1") (pinfunction "1_1") (pintype "passive"))
      (node (ref "R22") (pin "1") (pinfunction "1_1") (pintype "passive"))
      (node (ref "R26") (pin "1") (pinfunction "1_1") (pintype "passive"))
      (node (ref "R29") (pin "2") (pinfunction "2_2") (pintype "passive"))
      (node (ref "R3") (pin "1") (pinfunction "1_1") (pintype "passive"))
      (node (ref "R32") (pin "2") (pinfunction "2_2") (pintype "passive"))
      (node (ref "R39") (pin "1") (pinfunction "1_1") (pintype "passive"))
      (node (ref "R40") (pin "2") (pinfunction "2_2") (pintype "passive"))
      (node (ref "R42") (pin "1") (pinfunction "1_1") (pintype "passive"))
      (node (ref "R6") (pin "1") (pinfunction "1_1") (pintype "passive"))
      (node (ref "R9") (pin "1") (pinfunction "1_1") (pintype "passive"))
      (node (ref "RST") (pin "2") (pinfunction "2_2") (pintype "passive"))
      (node (ref "U1") (pin "11") (pinfunction "VSS_11") (pintype "passive"))
      (node (ref "U12") (pin "2") (pinfunction "GND_2") (pintype "passive"))
      (node (ref "U2") (pin "8") (pinfunction "COM_8") (pintype "passive"))
      (node (ref "U3") (pin "6") (pinfunction "GND_6") (pintype "passive"))
      (node (ref "U3") (pin "9") (pinfunction "PGND_9") (pintype "passive"))
      (node (ref "U4") (pin "2") (pinfunction "GND_2") (pintype "passive"))
      (node (ref "USB") (pin "1") (pinfunction "GND(A1+B12)_1") (pintype "passive"))
      (node (ref "USB") (pin "12") (pinfunction "GND(B1+A12)_12") (pintype "passive"))
      (node (ref "USB") (pin "SH1") (pinfunction "Shield1_SH1") (pintype "passive"))
      (node (ref "USB") (pin "SH2") (pinfunction "Shield2_SH2") (pintype "passive"))
      (node (ref "USB") (pin "SH3") (pinfunction "Shield3_SH3") (pintype "passive"))
      (node (ref "USB") (pin "SH4") (pinfunction "Shield4_SH4") (pintype "passive"))
      (node (ref "Y1") (pin "2") (pinfunction "GND_2") (pintype "passive"))
      (node (ref "Y1") (pin "4") (pinfunction "GND_4") (pintype "passive"))
    )
    (net (code "80") (name "Net-(C10-Pad1)") (class "Default")
      (node (ref "C10") (pin "1") (pinfunction "1_1") (pintype "passive"))
      (node (ref "R16") (pin "2") (pinfunction "2_2") (pintype "passive"))
      (node (ref "R17") (pin "1") (pinfunction "1_1") (pintype "passive"))
    )
    (net (code "81") (name "Net-(C10-Pad2)") (class "Default")
      (node (ref "C10") (pin "2") (pinfunction "2_2") (pintype "passive"))
      (node (ref "R18") (pin "2") (pinfunction "2_2") (pintype "passive"))
      (node (ref "R19") (pin "1") (pinfunction "1_1") (pintype "passive"))
    )
    (net (code "82") (name "Net-(C11-Pad1)") (class "Default")
      (node (ref "C11") (pin "1") (pinfunction "1_1") (pintype "passive"))
      (node (ref "R20") (pin "2") (pinfunction "2_2") (pintype "passive"))
      (node (ref "R21") (pin "1") (pinfunction "1_1") (pintype "passive"))
    )
    (net (code "83") (name "Net-(C11-Pad2)") (class "Default")
      (node (ref "C11") (pin "2") (pinfunction "2_2") (pintype "passive"))
      (node (ref "R22") (pin "2") (pinfunction "2_2") (pintype "passive"))
      (node (ref "R23") (pin "1") (pinfunction "1_1") (pintype "passive"))
    )
    (net (code "84") (name "Net-(C12-Pad1)") (class "Default")
      (node (ref "C12") (pin "1") (pinfunction "1_1") (pintype "passive"))
      (node (ref "R24") (pin "2") (pinfunction "2_2") (pintype "passive"))
      (node (ref "R25") (pin "1") (pinfunction "1_1") (pintype "passive"))
    )
    (net (code "85") (name "Net-(C12-Pad2)") (class "Default")
      (node (ref "C12") (pin "2") (pinfunction "2_2") (pintype "passive"))
      (node (ref "R26") (pin "2") (pinfunction "2_2") (pintype "passive"))
      (node (ref "R27") (pin "1") (pinfunction "1_1") (pintype "passive"))
    )
    (net (code "86") (name "Net-(C78-Pad1)") (class "Default")
      (node (ref "C78") (pin "1") (pinfunction "1_1") (pintype "passive"))
      (node (ref "H2") (pin "8") (pinfunction "8_8") (pintype "passive"))
      (node (ref "R62") (pin "1") (pinfunction "1_1") (pintype "passive"))
    )
    (net (code "87") (name "Net-(C79-Pad1)") (class "Default")
      (node (ref "C79") (pin "1") (pinfunction "1_1") (pintype "passive"))
      (node (ref "H2") (pin "7") (pinfunction "7_7") (pintype "passive"))
      (node (ref "R61") (pin "1") (pinfunction "1_1") (pintype "passive"))
    )
    (net (code "88") (name "Net-(C80-Pad1)") (class "Default")
      (node (ref "C80") (pin "1") (pinfunction "1_1") (pintype "passive"))
      (node (ref "H2") (pin "6") (pinfunction "6_6") (pintype "passive"))
      (node (ref "R60") (pin "1") (pinfunction "1_1") (pintype "passive"))
    )
    (net (code "89") (name "Net-(H2-Pad1)") (class "Default")
      (node (ref "H2") (pin "1") (pinfunction "1_1") (pintype "passive"))
      (node (ref "R54") (pin "1") (pinfunction "1_1") (pintype "passive"))
      (node (ref "R57") (pin "1") (pinfunction "1_1") (pintype "passive"))
    )
    (net (code "90") (name "Net-(H2-Pad2)") (class "Default")
      (node (ref "H2") (pin "2") (pinfunction "2_2") (pintype "passive"))
      (node (ref "R55") (pin "1") (pinfunction "1_1") (pintype "passive"))
      (node (ref "R58") (pin "1") (pinfunction "1_1") (pintype "passive"))
    )
    (net (code "91") (name "Net-(H2-Pad3)") (class "Default")
      (node (ref "H2") (pin "3") (pinfunction "3_3") (pintype "passive"))
      (node (ref "R56") (pin "1") (pinfunction "1_1") (pintype "passive"))
      (node (ref "R59") (pin "1") (pinfunction "1_1") (pintype "passive"))
    )
    (net (code "92") (name "Net-(Q1-G)") (class "Default")
      (node (ref "D2") (pin "1") (pintype "passive"))
      (node (ref "Q1") (pin "1") (pinfunction "G_1") (pintype "passive"))
      (node (ref "R1") (pin "2") (pinfunction "2_2") (pintype "passive"))
    )
    (net (code "93") (name "Net-(Q2-G)") (class "Default")
      (node (ref "D4") (pin "1") (pintype "passive"))
      (node (ref "Q2") (pin "1") (pinfunction "G_1") (pintype "passive"))
      (node (ref "R2") (pin "2") (pinfunction "2_2") (pintype "passive"))
    )
    (net (code "94") (name "Net-(Q3-G)") (class "Default")
      (node (ref "D6") (pin "1") (pintype "passive"))
      (node (ref "Q3") (pin "1") (pinfunction "G_1") (pintype "passive"))
      (node (ref "R4") (pin "2") (pinfunction "2_2") (pintype "passive"))
    )
    (net (code "95") (name "Net-(Q4-G)") (class "Default")
      (node (ref "D8") (pin "1") (pintype "passive"))
      (node (ref "Q4") (pin "1") (pinfunction "G_1") (pintype "passive"))
      (node (ref "R5") (pin "2") (pinfunction "2_2") (pintype "passive"))
    )
    (net (code "96") (name "Net-(Q5-G)") (class "Default")
      (node (ref "D11") (pin "1") (pintype "passive"))
      (node (ref "Q5") (pin "1") (pinfunction "G_1") (pintype "passive"))
      (node (ref "R7") (pin "2") (pinfunction "2_2") (pintype "passive"))
    )
    (net (code "97") (name "Net-(Q6-G)") (class "Default")
      (node (ref "D15") (pin "1") (pintype "passive"))
      (node (ref "Q6") (pin "1") (pinfunction "G_1") (pintype "passive"))
      (node (ref "R8") (pin "2") (pinfunction "2_2") (pintype "passive"))
    )
    (net (code "98") (name "Net-(R37-Pad1)") (class "Default")
      (node (ref "R37") (pin "1") (pinfunction "1_1") (pintype "passive"))
      (node (ref "R40") (pin "1") (pinfunction "1_1") (pintype "passive"))
      (node (ref "R41") (pin "2") (pinfunction "2_2") (pintype "passive"))
    )
    (net (code "99") (name "Net-(U3-BOOT)") (class "Default")
      (node (ref "C5") (pin "2") (pinfunction "2_2") (pintype "passive"))
      (node (ref "U3") (pin "1") (pinfunction "BOOT_1") (pintype "passive"))
    )
    (net (code "100") (name "Net-(U3-PH)") (class "Default")
      (node (ref "C5") (pin "1") (pinfunction "1_1") (pintype "passive"))
      (node (ref "D7") (pin "2") (pintype "passive"))
      (node (ref "L1") (pin "1") (pinfunction "1_1") (pintype "passive"))
      (node (ref "U3") (pin "8") (pinfunction "PH_8") (pintype "passive"))
    )
    (net (code "101") (name "Net-(U3-VSENSE)") (class "Default")
      (node (ref "R38") (pin "2") (pinfunction "2_2") (pintype "passive"))
      (node (ref "R39") (pin "2") (pinfunction "2_2") (pintype "passive"))
      (node (ref "U3") (pin "4") (pinfunction "VSENSE_4") (pintype "passive"))
    )
    (net (code "102") (name "Net-(USB-D+1(A6))") (class "Default")
      (node (ref "R33") (pin "1") (pinfunction "1_1") (pintype "passive"))
      (node (ref "R35") (pin "1") (pinfunction "1_1") (pintype "passive"))
      (node (ref "USB") (pin "6") (pinfunction "D+1(A6)_6") (pintype "passive"))
      (node (ref "USB") (pin "8") (pinfunction "D+2(B6)_8") (pintype "passive"))
    )
    (net (code "103") (name "Net-(USB-D-1(A7))") (class "Default")
      (node (ref "R34") (pin "1") (pinfunction "1_1") (pintype "passive"))
      (node (ref "USB") (pin "5") (pinfunction "D-2(B7)_5") (pintype "passive"))
      (node (ref "USB") (pin "7") (pinfunction "D-1(A7)_7") (pintype "passive"))
    )
    (net (code "104") (name "VBRG") (class "Default")
      (node (ref "D12") (pin "2") (pinfunction "K_2") (pintype "passive"))
      (node (ref "D9") (pin "2") (pinfunction "K_2") (pintype "passive"))
      (node (ref "Q1") (pin "2") (pinfunction "D_2") (pintype "passive"))
      (node (ref "Q3") (pin "2") (pinfunction "D_2") (pintype "passive"))
      (node (ref "Q5") (pin "2") (pinfunction "D_2") (pintype "passive"))
      (node (ref "R37") (pin "2") (pinfunction "2_2") (pintype "passive"))
    )
    (net (code "105") (name "VCC3.3V") (class "Default")
      (node (ref "C15") (pin "1") (pinfunction "1_1") (pintype "passive"))
      (node (ref "C24") (pin "1") (pinfunction "1_1") (pintype "passive"))
      (node (ref "C25") (pin "1") (pinfunction "1_1") (pintype "passive"))
      (node (ref "C26") (pin "1") (pinfunction "1_1") (pintype "passive"))
      (node (ref "C27") (pin "1") (pinfunction "1_1") (pintype "passive"))
      (node (ref "C61") (pin "1") (pinfunction "A_1") (pintype "passive"))
      (node (ref "C62") (pin "1") (pinfunction "1_1") (pintype "passive"))
      (node (ref "C69") (pin "1") (pinfunction "1_1") (pintype "passive"))
      (node (ref "D19") (pin "2") (pintype "passive"))
      (node (ref "D20") (pin "2") (pintype "passive"))
      (node (ref "D21") (pin "2") (pintype "passive"))
      (node (ref "DBG") (pin "6") (pinfunction "6_6") (pintype "passive"))
      (node (ref "IC") (pin "1") (pinfunction "VBAT_1") (pintype "passive"))
      (node (ref "IC") (pin "19") (pinfunction "VDD_19") (pintype "passive"))
      (node (ref "IC") (pin "32") (pinfunction "VDD_32") (pintype "passive"))
      (node (ref "IC") (pin "48") (pinfunction "VDD_48") (pintype "passive"))
      (node (ref "IC") (pin "64") (pinfunction "VDD_64") (pintype "passive"))
      (node (ref "R30") (pin "2") (pinfunction "2_2") (pintype "passive"))
      (node (ref "R31") (pin "1") (pinfunction "1_1") (pintype "passive"))
      (node (ref "R33") (pin "2") (pinfunction "2_2") (pintype "passive"))
      (node (ref "R36") (pin "1") (pinfunction "1_1") (pintype "passive"))
      (node (ref "R43") (pin "2") (pinfunction "2_2") (pintype "passive"))
      (node (ref "R54") (pin "2") (pinfunction "2_2") (pintype "passive"))
      (node (ref "R55") (pin "2") (pinfunction "2_2") (pintype "passive"))
      (node (ref "R56") (pin "2") (pinfunction "2_2") (pintype "passive"))
      (node (ref "U12") (pin "5") (pinfunction "OUT_5") (pintype "passive"))
    )
    (net (code "106") (name "VCC5V") (class "Default")
      (node (ref "C60") (pin "1") (pinfunction "1_1") (pintype "passive"))
      (node (ref "C68") (pin "1") (pinfunction "1_1") (pintype "passive"))
      (node (ref "C88") (pin "1") (pinfunction "A_1") (pintype "passive"))
      (node (ref "D3") (pin "2") (pintype "passive"))
      (node (ref "H2") (pin "5") (pinfunction "5_5") (pintype "passive"))
      (node (ref "OLED") (pin "2") (pinfunction "2_2") (pintype "passive"))
      (node (ref "U12") (pin "1") (pinfunction "VIN_1") (pintype "passive"))
      (node (ref "U12") (pin "3") (pinfunction "EN_3") (pintype "passive"))
      (node (ref "U4") (pin "3") (pinfunction "VOUT_3") (pintype "passive"))
    )
    (net (code "107") (name "VCC10V") (class "Default")
      (node (ref "C4") (pin "2") (pinfunction "2_2") (pintype "passive"))
      (node (ref "C6") (pin "1") (pinfunction "A_1") (pintype "passive"))
      (node (ref "C7") (pin "2") (pinfunction "2_2") (pintype "passive"))
      (node (ref "C8") (pin "2") (pinfunction "2_2") (pintype "passive"))
      (node (ref "D1") (pin "1") (pintype "passive"))
      (node (ref "D10") (pin "1") (pintype "passive"))
      (node (ref "D5") (pin "1") (pintype "passive"))
      (node (ref "L1") (pin "2") (pinfunction "2_2") (pintype "passive"))
      (node (ref "R38") (pin "1") (pinfunction "1_1") (pintype "passive"))
      (node (ref "U2") (pin "7") (pinfunction "VCC_7") (pintype "passive"))
      (node (ref "U4") (pin "1") (pinfunction "VIN_1") (pintype "passive"))
    )
    (net (code "108") (name "VPWR") (class "Default")
      (node (ref "C28") (pin "2") (pinfunction "2_2") (pintype "passive"))
      (node (ref "C29") (pin "2") (pinfunction "2_2") (pintype "passive"))
      (node (ref "C30") (pin "1") (pinfunction "A_1") (pintype "passive"))
      (node (ref "C9") (pin "1") (pinfunction "A_1") (pintype "passive"))
      (node (ref "D12") (pin "1") (pinfunction "A_1") (pintype "passive"))
      (node (ref "D9") (pin "1") (pinfunction "A_1") (pintype "passive"))
      (node (ref "DC_IN") (pin "1") (pintype "power_in"))
      (node (ref "H1") (pin "1") (pinfunction "1_1") (pintype "passive"))
      (node (ref "U3") (pin "7") (pinfunction "VIN_7") (pintype "passive"))
    )
    (net (code "109") (name "VUSB") (class "Default")
      (node (ref "D3") (pin "1") (pintype "passive"))
      (node (ref "USB") (pin "11") (pinfunction "VBUS(B4+A9)_11") (pintype "passive"))
      (node (ref "USB") (pin "2") (pinfunction "VBUS(A4+B9)_2") (pintype "passive"))
    )
    (net (code "110") (name "unconnected-(HOLE1-Pad1)") (class "Default")
      (node (ref "HOLE1") (pin "1") (pintype "passive"))
    )
    (net (code "111") (name "unconnected-(HOLE2-Pad1)") (class "Default")
      (node (ref "HOLE2") (pin "1") (pintype "passive"))
    )
    (net (code "112") (name "unconnected-(HOLE3-Pad1)") (class "Default")
      (node (ref "HOLE3") (pin "1") (pintype "passive"))
    )
    (net (code "113") (name "unconnected-(HOLE4-Pad1)") (class "Default")
      (node (ref "HOLE4") (pin "1") (pintype "passive"))
    )
    (net (code "114") (name "unconnected-(U3-ENA-Pad5)") (class "Default")
      (node (ref "U3") (pin "5") (pinfunction "ENA_5") (pintype "passive+no_connect"))
    )
    (net (code "115") (name "unconnected-(U3-NC-Pad2)") (class "Default")
      (node (ref "U3") (pin "2") (pinfunction "NC_2") (pintype "passive+no_connect"))
    )
    (net (code "116") (name "unconnected-(U3-NC-Pad3)") (class "Default")
      (node (ref "U3") (pin "3") (pinfunction "NC_3") (pintype "passive+no_connect"))
    )
    (net (code "117") (name "unconnected-(U12-BP-Pad4)") (class "Default")
      (node (ref "U12") (pin "4") (pinfunction "BP_4") (pintype "passive+no_connect"))
    )
    (net (code "118") (name "unconnected-(USB-CC1(A5)-Pad4)") (class "Default")
      (node (ref "USB") (pin "4") (pinfunction "CC1(A5)_4") (pintype "passive"))
    )
    (net (code "119") (name "unconnected-(USB-CC2(B5)-Pad10)") (class "Default")
      (node (ref "USB") (pin "10") (pinfunction "CC2(B5)_10") (pintype "passive"))
    )
    (net (code "120") (name "unconnected-(USB-SBU1(A8)-Pad9)") (class "Default")
      (node (ref "USB") (pin "9") (pinfunction "SBU1(A8)_9") (pintype "passive"))
    )
    (net (code "121") (name "unconnected-(USB-SBU2(B8)-Pad3)") (class "Default")
      (node (ref "USB") (pin "3") (pinfunction "SBU2(B8)_3") (pintype "passive"))
    )
  )
)
